# Regulator3V3.net
KiCad netlist of a schematic drawn in Altium Designer
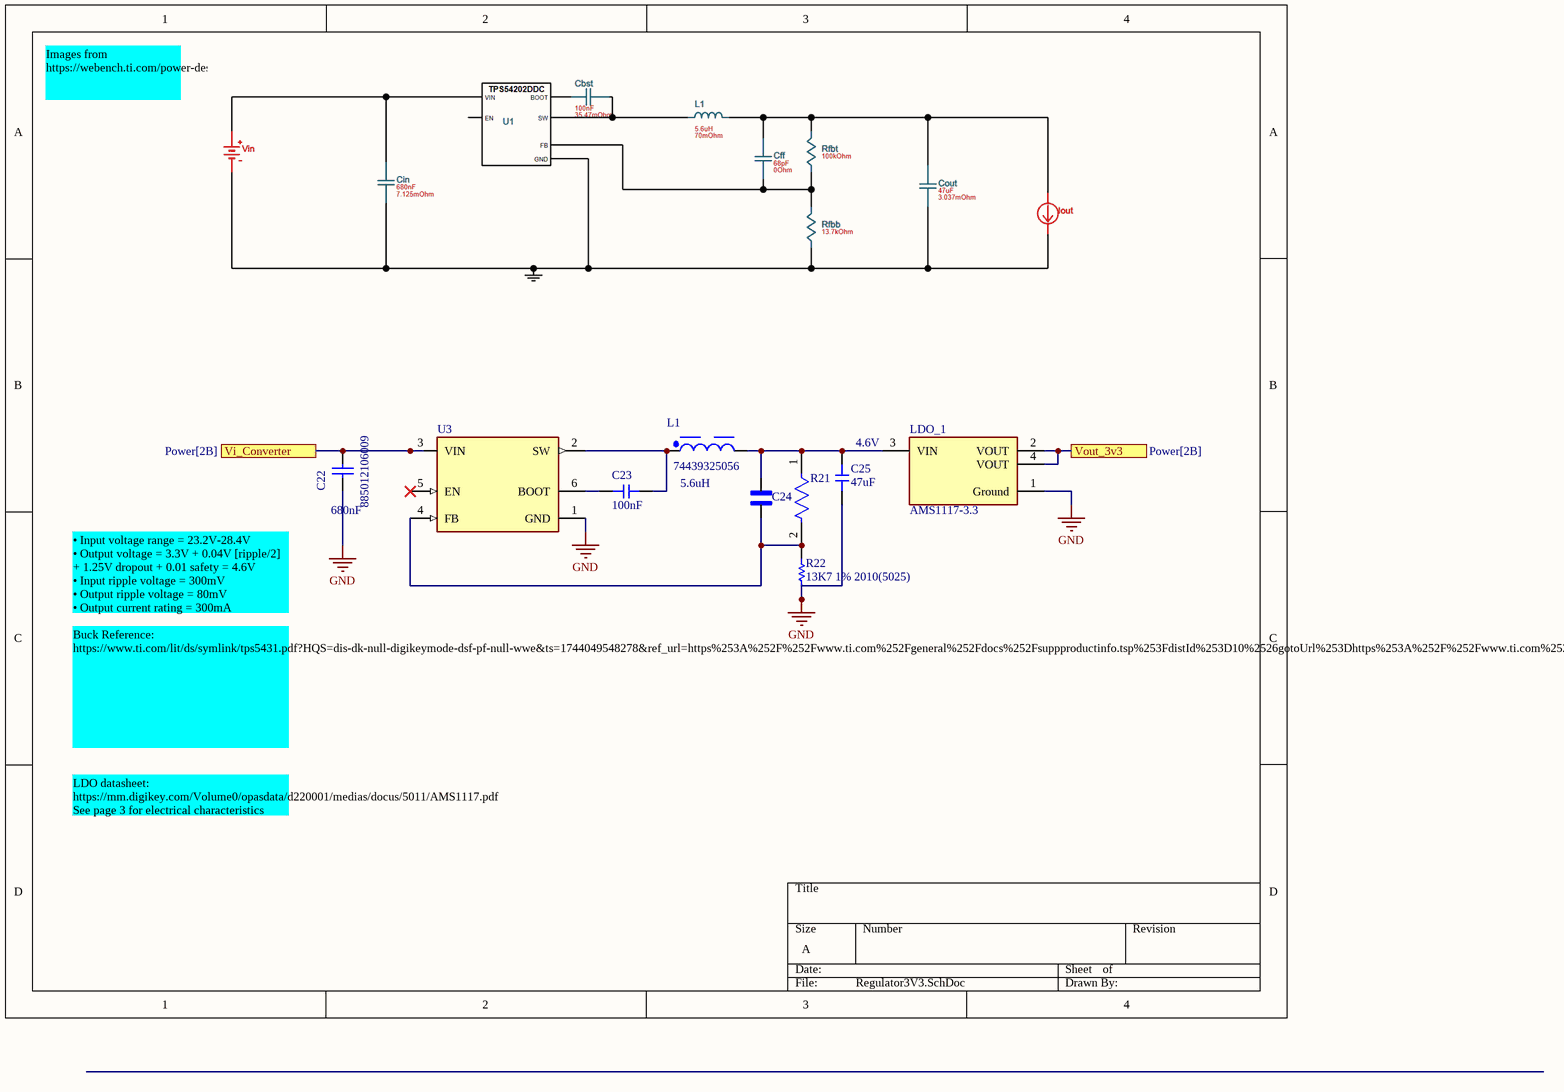
[diagram p0: Regulator3V3.SchDoc]

(export (version "E")
  (design (tool "Eeschema 10.0.6"))
  (components
    (comp (ref "C22")
      (value "885012106009")
      (footprint "WCAP-CSGP_0603_L1.6W0.8H0.8_Reflow")
      (description "Cap Cer 0.68UF 10V X5R 0603")
      (fields (field (name "TOLERANCE") "20%") (field (name "CAPACITANCE") "680nF"))
      (libsource (lib "Altium Content Vault") (part "Capacitor_Non-Polarized"))
    )
    (comp (ref "C23")
      (value "CL05B104KO5NNNC")
      (footprint "CAP-0402")
      (description "Capacitor, Ceramic (MLCC), 100nF, ±10%, 16V, X7R, ±10%, SMD 0402")
      (fields
        (field (name "JLCPCB BASIC PART") "Yes")
        (field (name "CAPACITANCE") "100nF")
        (field (name "JLCPCB PART NUMBER") "C1525")
      )
      (libsource (lib "jlcpcb_2024_10_capacitors_basic") (part "CL05B104KO5NNNC"))
    )
    (comp (ref "C24")
      (value "CGA1A2C0G1E680J030BA")
      (footprint "CAPC0603X33N")
      (description "68 pF Â±5% 25V Ceramic Capacitor C0G, NP0 0201 (0603 Metric)")
      (fields (field (name "MF") "TDK"))
      (libsource (lib "CGA1A2C0G1E680J030BA") (part "CGA1A2C0G1E680J030BA"))
    )
    (comp (ref "C25")
      (value "CL21A476MQYNNNE")
      (footprint "CAP-0805")
      (description "Capacitor, Ceramic (MLCC), 47uF, ±20%, 6.3V, X5R, ±20%, SMD 0805")
      (fields
        (field (name "JLCPCB BASIC PART") "Yes")
        (field (name "CAPACITANCE") "47uF")
        (field (name "JLCPCB PART NUMBER") "C16780")
      )
      (libsource (lib "jlcpcb_2024_10_capacitors_basic") (part "CL21A476MQYNNNE"))
    )
    (comp (ref "L1")
      (value "74439325056")
      (footprint "WE-XHMI_4040")
      (description "Power Inductor, 5.6UH, Shielded, 5.1A Rohs Compliant: Yes")
      (fields (field (name "PARAMETER 1") "5.6uH"))
      (libsource (lib "Altium Content Vault") (part "Inductor - 2"))
    )
    (comp (ref "LDO_1")
      (value "AMS1117-3.3")
      (footprint "FP-AMS1117-IPC_C")
      (description "LDO Voltage Regulators 1A, 3.3V")
      (fields
        (field (name "OCTOPART") "https://octopart.com/ams1117-3.3-advanced+monolithic+systems-25899300")
        (field (name "MANUFACTURER") "Advanced Monolithic Systems")
      )
      (libsource (lib "Altium Content Vault") (part "8bdbb5f8e77002000e30dd2845d0354"))
    )
    (comp (ref "R21")
      (value "~")
      (footprint "FP-CRCW0603-e3-MFG")
      (description "RES Thick Film, 100kΩ, 1%, 0.1W, 100ppm/°C, 0603")
      (fields (field (name "TOLERANCE") "1%"))
      (libsource (lib "Res21 - 01.02.26 - 16") (part "CMP-02407-005189-1"))
    )
    (comp (ref "R22")
      (value "13K7 1% 2010(5025)")
      (footprint "RESC2010(5025)_N")
      (description "13K7 0.75W 1% 2010 (5025 Metric)  SMD")
      (fields (field (name "POWER") "0.75 W") (field (name "TOLERANCE") "1 %"))
      (libsource (lib "Altium Content Vault") (part "RES"))
    )
    (comp (ref "U3")
      (value "~")
      (footprint "FP-DDC0006A-IPC_A")
      (description "IC REG BUCK ADJ 2A TSOT23-6")
      (libsource (lib "tps54202ddcr") (part "35c2d3f1afc239a386b2ba50eead654"))
    )
  )
  (nets
    (net (code "1") (name "/Vi_Converter") (class "Default")
      (node (ref "C22") (pin "2") (pinfunction "2_2") (pintype "passive"))
      (node (ref "U3") (pin "3") (pinfunction "VIN_3") (pintype "power_in"))
    )
    (net (code "2") (name "/Vout_3v3") (class "Default")
      (node (ref "LDO_1") (pin "2") (pinfunction "VOUT_2") (pintype "passive"))
      (node (ref "LDO_1") (pin "4") (pinfunction "VOUT_4") (pintype "passive"))
    )
    (net (code "3") (name "GND") (class "Default")
      (node (ref "C22") (pin "1") (pinfunction "1_1") (pintype "passive"))
      (node (ref "C25") (pin "1") (pinfunction "1_1") (pintype "passive"))
      (node (ref "LDO_1") (pin "1") (pinfunction "Ground_1") (pintype "power_in"))
      (node (ref "R22") (pin "1") (pinfunction "1_1") (pintype "passive"))
      (node (ref "U3") (pin "1") (pinfunction "GND_1") (pintype "power_in"))
    )
    (net (code "4") (name "Net-(LDO_1-VIN)") (class "Default")
      (node (ref "C24") (pin "2") (pinfunction "2_2") (pintype "passive"))
      (node (ref "C25") (pin "2") (pinfunction "2_2") (pintype "passive"))
      (node (ref "L1") (pin "2") (pinfunction "2_2") (pintype "passive"))
      (node (ref "LDO_1") (pin "3") (pinfunction "VIN_3") (pintype "power_in"))
      (node (ref "R21") (pin "1") (pinfunction "1_1") (pintype "passive"))
    )
    (net (code "5") (name "Net-(U3-BOOT)") (class "Default")
      (node (ref "C23") (pin "1") (pinfunction "1_1") (pintype "passive"))
      (node (ref "U3") (pin "6") (pinfunction "BOOT_6") (pintype "passive"))
    )
    (net (code "6") (name "Net-(U3-FB)") (class "Default")
      (node (ref "C24") (pin "1") (pinfunction "1_1") (pintype "passive"))
      (node (ref "R21") (pin "2") (pinfunction "2_2") (pintype "passive"))
      (node (ref "R22") (pin "2") (pinfunction "2_2") (pintype "passive"))
      (node (ref "U3") (pin "4") (pinfunction "FB_4") (pintype "input"))
    )
    (net (code "7") (name "Net-(U3-SW)") (class "Default")
      (node (ref "C23") (pin "2") (pinfunction "2_2") (pintype "passive"))
      (node (ref "L1") (pin "1") (pinfunction "1_1") (pintype "passive"))
      (node (ref "U3") (pin "2") (pinfunction "SW_2") (pintype "output"))
    )
    (net (code "8") (name "unconnected-(U3-EN-Pad5)") (class "Default")
      (node (ref "U3") (pin "5") (pinfunction "EN_5") (pintype "input+no_connect"))
    )
  )
)
